# Sheet_1_2025-01-28.net
KiCad netlist of a schematic drawn in Altium Designer
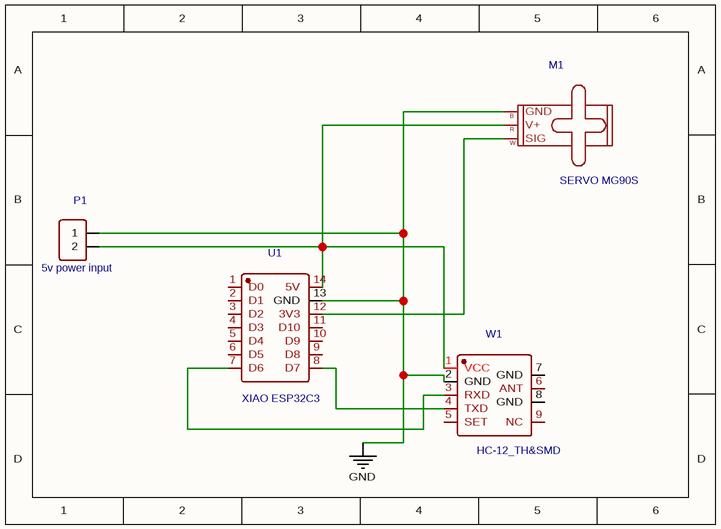
[diagram p0: Sheet_1_2025-01-28.schdoc]

(export (version "E")
  (design (tool "Eeschema 10.0.6"))
  (components
    (comp (ref "M1")
      (value "SERVO MG90S")
      (description "Small servo motor")
      (fields (field (name "CONTRIBUTOR") "SparkFun"))
      (libsource (lib "altium-import") (part "root_2_SERVO MG90S_"))
    )
    (comp (ref "P1")
      (value "5v power input")
      (fields (field (name "CONTRIBUTOR") "LCEDA_Lib"))
      (libsource (lib "altium-import") (part "root_0_5v power input_"))
    )
    (comp (ref "U1")
      (value "XIAO ESP32C3")
      (fields (field (name "CONTRIBUTOR") "lcsc"))
      (libsource (lib "altium-import") (part "root_0_XIAO ESP32C3_"))
    )
    (comp (ref "W1")
      (value "HC-12_TH&SMD")
      (fields (field (name "CONTRIBUTOR") "lcsc"))
      (libsource (lib "altium-import") (part "root_0_HC-12_TH&SMD_"))
    )
  )
  (nets
    (net (code "1") (name "GND") (class "Default")
      (node (ref "M1") (pin "3") (pinfunction "GND_3") (pintype "passive"))
      (node (ref "P1") (pin "1") (pinfunction "1_1") (pintype "passive"))
      (node (ref "U1") (pin "13") (pinfunction "GND_13") (pintype "passive"))
      (node (ref "W1") (pin "2") (pinfunction "GND_2") (pintype "passive"))
    )
    (net (code "2") (name "Net-(M1-SIG)") (class "Default")
      (node (ref "M1") (pin "1") (pinfunction "SIG_1") (pintype "passive"))
      (node (ref "U1") (pin "12") (pinfunction "3V3_12") (pintype "passive"))
    )
    (net (code "3") (name "Net-(M1-V+)") (class "Default")
      (node (ref "M1") (pin "2") (pinfunction "V+_2") (pintype "passive"))
      (node (ref "P1") (pin "2") (pinfunction "2_2") (pintype "passive"))
      (node (ref "U1") (pin "14") (pinfunction "5V_14") (pintype "passive"))
      (node (ref "W1") (pin "1") (pinfunction "VCC_1") (pintype "passive"))
    )
    (net (code "4") (name "Net-(U1-D6)") (class "Default")
      (node (ref "U1") (pin "7") (pinfunction "D6_7") (pintype "passive"))
      (node (ref "W1") (pin "3") (pinfunction "RXD_3") (pintype "passive"))
    )
    (net (code "5") (name "Net-(U1-D7)") (class "Default")
      (node (ref "U1") (pin "8") (pinfunction "D7_8") (pintype "passive"))
      (node (ref "W1") (pin "4") (pinfunction "TXD_4") (pintype "passive"))
    )
    (net (code "6") (name "unconnected-(U1-D0-Pad1)") (class "Default")
      (node (ref "U1") (pin "1") (pinfunction "D0_1") (pintype "passive"))
    )
    (net (code "7") (name "unconnected-(U1-D1-Pad2)") (class "Default")
      (node (ref "U1") (pin "2") (pinfunction "D1_2") (pintype "passive"))
    )
    (net (code "8") (name "unconnected-(U1-D2-Pad3)") (class "Default")
      (node (ref "U1") (pin "3") (pinfunction "D2_3") (pintype "passive"))
    )
    (net (code "9") (name "unconnected-(U1-D3-Pad4)") (class "Default")
      (node (ref "U1") (pin "4") (pinfunction "D3_4") (pintype "passive"))
    )
    (net (code "10") (name "unconnected-(U1-D4-Pad5)") (class "Default")
      (node (ref "U1") (pin "5") (pinfunction "D4_5") (pintype "passive"))
    )
    (net (code "11") (name "unconnected-(U1-D5-Pad6)") (class "Default")
      (node (ref "U1") (pin "6") (pinfunction "D5_6") (pintype "passive"))
    )
    (net (code "12") (name "unconnected-(U1-D8-Pad9)") (class "Default")
      (node (ref "U1") (pin "9") (pinfunction "D8_9") (pintype "passive"))
    )
    (net (code "13") (name "unconnected-(U1-D9-Pad10)") (class "Default")
      (node (ref "U1") (pin "10") (pinfunction "D9_10") (pintype "passive"))
    )
    (net (code "14") (name "unconnected-(U1-D10-Pad11)") (class "Default")
      (node (ref "U1") (pin "11") (pinfunction "D10_11") (pintype "passive"))
    )
    (net (code "15") (name "unconnected-(W1-ANT-Pad6)") (class "Default")
      (node (ref "W1") (pin "6") (pinfunction "ANT_6") (pintype "passive"))
    )
    (net (code "16") (name "unconnected-(W1-GND-Pad7)") (class "Default")
      (node (ref "W1") (pin "7") (pinfunction "GND_7") (pintype "passive"))
    )
    (net (code "17") (name "unconnected-(W1-GND-Pad8)") (class "Default")
      (node (ref "W1") (pin "8") (pinfunction "GND_8") (pintype "passive"))
    )
    (net (code "18") (name "unconnected-(W1-NC-Pad9)") (class "Default")
      (node (ref "W1") (pin "9") (pinfunction "NC_9") (pintype "passive"))
    )
    (net (code "19") (name "unconnected-(W1-SET-Pad5)") (class "Default")
      (node (ref "W1") (pin "5") (pinfunction "SET_5") (pintype "passive"))
    )
  )
)
